# match3.net
KiCad netlist of a schematic drawn in EAGLE
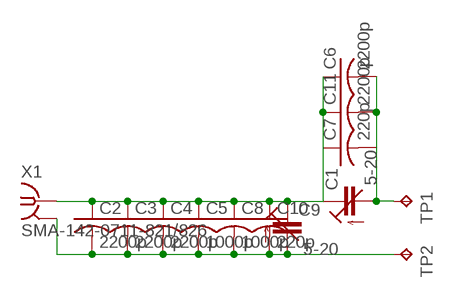
[diagram p0: schematic, sheet 1]

(export (version "E")
  (design (tool "Eeschema 10.0.6"))
  (components
    (comp (ref "C1")
      (value "5-20")
      (footprint "eagle-import:SGC3S")
      (libsource (lib "eagle-import") (part "C-TRIMM"))
    )
    (comp (ref "C2")
      (value "2200p")
      (footprint "eagle-import:C0805")
      (libsource (lib "eagle-import") (part "C-USC0805"))
    )
    (comp (ref "C3")
      (value "2200p")
      (footprint "eagle-import:C0805")
      (libsource (lib "eagle-import") (part "C-USC0805"))
    )
    (comp (ref "C4")
      (value "2200p")
      (footprint "eagle-import:C0805")
      (libsource (lib "eagle-import") (part "C-USC0805"))
    )
    (comp (ref "C5")
      (value "1000p")
      (footprint "eagle-import:C0805")
      (libsource (lib "eagle-import") (part "C-USC0805"))
    )
    (comp (ref "C6")
      (value "2200p")
      (footprint "eagle-import:C0805")
      (libsource (lib "eagle-import") (part "C-USC0805"))
    )
    (comp (ref "C7")
      (value "220p")
      (footprint "eagle-import:C0805")
      (libsource (lib "eagle-import") (part "C-USC0805"))
    )
    (comp (ref "C8")
      (value "1000p")
      (footprint "eagle-import:C0805")
      (libsource (lib "eagle-import") (part "C-USC0805"))
    )
    (comp (ref "C9")
      (value "5-20")
      (footprint "eagle-import:SGC3S")
      (libsource (lib "eagle-import") (part "C-TRIMM"))
    )
    (comp (ref "C10")
      (value "220p")
      (footprint "eagle-import:C0805")
      (libsource (lib "eagle-import") (part "C-USC0805"))
    )
    (comp (ref "C11")
      (value "2200p")
      (footprint "eagle-import:C0805")
      (libsource (lib "eagle-import") (part "C-USC0805"))
    )
    (comp (ref "TP1")
      (value "TPPAD1-13Y")
      (footprint "eagle-import:P1-13Y")
      (libsource (lib "eagle-import") (part "TPPAD1-13Y"))
    )
    (comp (ref "TP2")
      (value "TPPAD1-13Y")
      (footprint "eagle-import:P1-13Y")
      (libsource (lib "eagle-import") (part "TPPAD1-13Y"))
    )
    (comp (ref "X1")
      (value "SMA-142-0711-821/826")
      (footprint "eagle-import:J502-ND-142-0711-821_826")
      (fields (field (name "MF") "JOHNSON COMPONENTS") (field (name "MPN") "142-0711-821"))
      (libsource (lib "eagle-import") (part "SMA-142-0711-821/826"))
    )
  )
  (nets
    (net (code "1") (name "Net-(C1-A)") (class "Default")
      (node (ref "C1") (pin "P$1") (pinfunction "A_P$1") (pintype "passive"))
      (node (ref "C11") (pin "2") (pinfunction "2_2") (pintype "passive"))
      (node (ref "C6") (pin "2") (pinfunction "2_2") (pintype "passive"))
      (node (ref "C7") (pin "2") (pinfunction "2_2") (pintype "passive"))
      (node (ref "TP1") (pin "TP") (pinfunction "TP_TP") (pintype "input"))
    )
    (net (code "2") (name "Net-(C1-E)") (class "Default")
      (node (ref "C1") (pin "P$2") (pinfunction "E_P$2") (pintype "passive"))
      (node (ref "C10") (pin "1") (pinfunction "1_1") (pintype "passive"))
      (node (ref "C11") (pin "1") (pinfunction "1_1") (pintype "passive"))
      (node (ref "C2") (pin "1") (pinfunction "1_1") (pintype "passive"))
      (node (ref "C3") (pin "1") (pinfunction "1_1") (pintype "passive"))
      (node (ref "C4") (pin "1") (pinfunction "1_1") (pintype "passive"))
      (node (ref "C5") (pin "1") (pinfunction "1_1") (pintype "passive"))
      (node (ref "C6") (pin "1") (pinfunction "1_1") (pintype "passive"))
      (node (ref "C7") (pin "1") (pinfunction "1_1") (pintype "passive"))
      (node (ref "C8") (pin "1") (pinfunction "1_1") (pintype "passive"))
      (node (ref "C9") (pin "P$2") (pinfunction "E_P$2") (pintype "passive"))
      (node (ref "X1") (pin "1") (pinfunction "1_1") (pintype "passive"))
    )
    (net (code "3") (name "Net-(C9-A)") (class "Default")
      (node (ref "C10") (pin "2") (pinfunction "2_2") (pintype "passive"))
      (node (ref "C2") (pin "2") (pinfunction "2_2") (pintype "passive"))
      (node (ref "C3") (pin "2") (pinfunction "2_2") (pintype "passive"))
      (node (ref "C4") (pin "2") (pinfunction "2_2") (pintype "passive"))
      (node (ref "C5") (pin "2") (pinfunction "2_2") (pintype "passive"))
      (node (ref "C8") (pin "2") (pinfunction "2_2") (pintype "passive"))
      (node (ref "C9") (pin "P$1") (pinfunction "A_P$1") (pintype "passive"))
      (node (ref "TP2") (pin "TP") (pinfunction "TP_TP") (pintype "input"))
      (node (ref "X1") (pin "G@1") (pinfunction "2_G@1") (pintype "passive"))
      (node (ref "X1") (pin "G@2") (pinfunction "2_G@2") (pintype "passive"))
      (node (ref "X1") (pin "G@3") (pinfunction "2_G@3") (pintype "passive"))
      (node (ref "X1") (pin "G@4") (pinfunction "2_G@4") (pintype "passive"))
    )
  )
)
